# OpenHAS_SensorBoard_v1_0.net
KiCad netlist of a schematic drawn in EAGLE
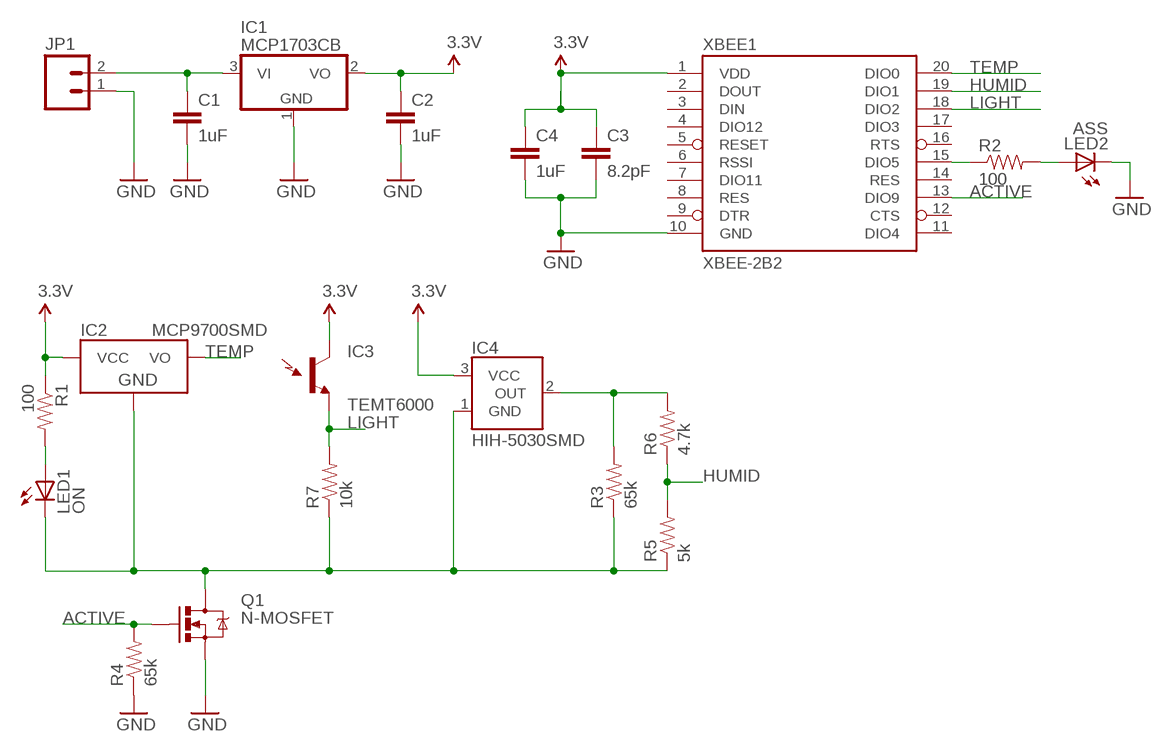
[diagram p0: schematic, sheet 1]

(export (version "E")
  (design (tool "Eeschema 10.0.6"))
  (components
    (comp (ref "C1")
      (value "1uF")
      (footprint "eagle-import:0805")
      (libsource (lib "eagle-import") (part "CAP0805"))
    )
    (comp (ref "C2")
      (value "1uF")
      (footprint "eagle-import:0805")
      (libsource (lib "eagle-import") (part "CAP0805"))
    )
    (comp (ref "C3")
      (value "8.2pF")
      (footprint "eagle-import:0805")
      (libsource (lib "eagle-import") (part "CAP0805"))
    )
    (comp (ref "C4")
      (value "1uF")
      (footprint "eagle-import:0805")
      (libsource (lib "eagle-import") (part "CAP0805"))
    )
    (comp (ref "IC1")
      (value "MCP1703CB")
      (footprint "eagle-import:SOT23")
      (libsource (lib "eagle-import") (part "MCP1703CB"))
    )
    (comp (ref "IC2")
      (value "MCP9700SMD")
      (footprint "eagle-import:SOT23-3")
      (libsource (lib "eagle-import") (part "MCP9700SMD"))
    )
    (comp (ref "IC3")
      (value "TEMT6000")
      (footprint "eagle-import:TEMT6000-SEN")
      (libsource (lib "eagle-import") (part "LIGHTSENSORTEMT6000"))
    )
    (comp (ref "IC4")
      (value "HIH-5030SMD")
      (footprint "eagle-import:HIH-4030")
      (libsource (lib "eagle-import") (part "HIH-4030SMD"))
    )
    (comp (ref "JP1")
      (value "M02POLAR")
      (footprint "eagle-import:MOLEX-1X2")
      (libsource (lib "eagle-import") (part "M02POLAR"))
    )
    (comp (ref "LED1")
      (value "ON")
      (footprint "eagle-import:CHIP-LED0805")
      (libsource (lib "eagle-import") (part "LEDCHIP-LED0805"))
    )
    (comp (ref "LED2")
      (value "ASS")
      (footprint "eagle-import:CHIP-LED0805")
      (libsource (lib "eagle-import") (part "LEDCHIP-LED0805"))
    )
    (comp (ref "Q1")
      (value "N-MOSFET")
      (footprint "eagle-import:SOT23-3")
      (libsource (lib "eagle-import") (part "MOSFET-NCHANNELAO3404A"))
    )
    (comp (ref "R1")
      (value "100")
      (footprint "eagle-import:0805")
      (libsource (lib "eagle-import") (part "RESISTOR0805-RES"))
    )
    (comp (ref "R2")
      (value "100")
      (footprint "eagle-import:0805")
      (libsource (lib "eagle-import") (part "SparkFun-Resistors_RESISTOR0805-RES"))
    )
    (comp (ref "R3")
      (value "65k")
      (footprint "eagle-import:0805")
      (libsource (lib "eagle-import") (part "SparkFun-Resistors_RESISTOR0805-RES"))
    )
    (comp (ref "R4")
      (value "65k")
      (footprint "eagle-import:0805")
      (libsource (lib "eagle-import") (part "SparkFun-Resistors_RESISTOR0805-RES"))
    )
    (comp (ref "R5")
      (value "5k")
      (footprint "eagle-import:0805")
      (libsource (lib "eagle-import") (part "SparkFun-Resistors_RESISTOR0805-RES"))
    )
    (comp (ref "R6")
      (value "4.7k")
      (footprint "eagle-import:0805")
      (libsource (lib "eagle-import") (part "SparkFun-Resistors_RESISTOR0805-RES"))
    )
    (comp (ref "R7")
      (value "10k")
      (footprint "eagle-import:0805")
      (libsource (lib "eagle-import") (part "SparkFun-Resistors_RESISTOR0805-RES"))
    )
    (comp (ref "XBEE1")
      (value "XBEE-2B2")
      (footprint "eagle-import:XBEE-SILK")
      (libsource (lib "eagle-import") (part "XBEE-2B2"))
    )
  )
  (nets
    (net (code "1") (name "/ACTIVE") (class "Default")
      (node (ref "Q1") (pin "1") (pinfunction "G_1") (pintype "passive"))
      (node (ref "R4") (pin "2") (pinfunction "2_2") (pintype "passive"))
      (node (ref "XBEE1") (pin "13") (pinfunction "DIO9_13") (pintype "bidirectional"))
    )
    (net (code "2") (name "/HUMID") (class "Default")
      (node (ref "R5") (pin "2") (pinfunction "2_2") (pintype "passive"))
      (node (ref "R6") (pin "1") (pinfunction "1_1") (pintype "passive"))
      (node (ref "XBEE1") (pin "19") (pinfunction "DIO1_19") (pintype "bidirectional"))
    )
    (net (code "3") (name "/LIGHT") (class "Default")
      (node (ref "IC3") (pin "EMITTER") (pinfunction "E1_EMITTER") (pintype "passive"))
      (node (ref "R7") (pin "2") (pinfunction "2_2") (pintype "passive"))
      (node (ref "XBEE1") (pin "18") (pinfunction "DIO2_18") (pintype "bidirectional"))
    )
    (net (code "4") (name "/TEMP") (class "Default")
      (node (ref "IC2") (pin "2") (pinfunction "VO_2") (pintype "bidirectional"))
      (node (ref "XBEE1") (pin "20") (pinfunction "DIO0_20") (pintype "bidirectional"))
    )
    (net (code "5") (name "3.3V") (class "Default")
      (node (ref "C2") (pin "1") (pinfunction "1_1") (pintype "passive"))
      (node (ref "C3") (pin "1") (pinfunction "1_1") (pintype "passive"))
      (node (ref "C4") (pin "1") (pinfunction "1_1") (pintype "passive"))
      (node (ref "IC1") (pin "2") (pinfunction "VO_2") (pintype "passive"))
      (node (ref "IC2") (pin "1") (pinfunction "VCC_1") (pintype "bidirectional"))
      (node (ref "IC3") (pin "COLLECTOR") (pinfunction "C1_COLLECTOR") (pintype "passive"))
      (node (ref "IC4") (pin "3") (pinfunction "VCC_3") (pintype "bidirectional"))
      (node (ref "R1") (pin "1") (pinfunction "1_1") (pintype "passive"))
      (node (ref "XBEE1") (pin "1") (pinfunction "VDD_1") (pintype "power_in"))
    )
    (net (code "6") (name "GND") (class "Default")
      (node (ref "C1") (pin "2") (pinfunction "2_2") (pintype "passive"))
      (node (ref "C2") (pin "2") (pinfunction "2_2") (pintype "passive"))
      (node (ref "C3") (pin "2") (pinfunction "2_2") (pintype "passive"))
      (node (ref "C4") (pin "2") (pinfunction "2_2") (pintype "passive"))
      (node (ref "IC1") (pin "1") (pinfunction "GND_1") (pintype "passive"))
      (node (ref "JP1") (pin "1") (pinfunction "1_1") (pintype "passive"))
      (node (ref "LED2") (pin "C") (pinfunction "C_C") (pintype "passive"))
      (node (ref "Q1") (pin "2") (pinfunction "S_2") (pintype "passive"))
      (node (ref "R4") (pin "1") (pinfunction "1_1") (pintype "passive"))
      (node (ref "XBEE1") (pin "10") (pinfunction "GND_10") (pintype "power_in"))
    )
    (net (code "7") (name "Net-(IC1-VI)") (class "Default")
      (node (ref "C1") (pin "1") (pinfunction "1_1") (pintype "passive"))
      (node (ref "IC1") (pin "3") (pinfunction "VI_3") (pintype "input"))
      (node (ref "JP1") (pin "2") (pinfunction "2_2") (pintype "passive"))
    )
    (net (code "8") (name "Net-(IC2-GND)") (class "Default")
      (node (ref "IC2") (pin "3") (pinfunction "GND_3") (pintype "bidirectional"))
      (node (ref "IC4") (pin "1") (pinfunction "GND_1") (pintype "bidirectional"))
      (node (ref "LED1") (pin "C") (pinfunction "C_C") (pintype "passive"))
      (node (ref "Q1") (pin "3") (pinfunction "D_3") (pintype "passive"))
      (node (ref "R3") (pin "1") (pinfunction "1_1") (pintype "passive"))
      (node (ref "R5") (pin "1") (pinfunction "1_1") (pintype "passive"))
      (node (ref "R7") (pin "1") (pinfunction "1_1") (pintype "passive"))
    )
    (net (code "9") (name "Net-(IC4-OUT)") (class "Default")
      (node (ref "IC4") (pin "2") (pinfunction "OUT_2") (pintype "bidirectional"))
      (node (ref "R3") (pin "2") (pinfunction "2_2") (pintype "passive"))
      (node (ref "R6") (pin "2") (pinfunction "2_2") (pintype "passive"))
    )
    (net (code "10") (name "Net-(LED1-PadA)") (class "Default")
      (node (ref "LED1") (pin "A") (pinfunction "A_A") (pintype "passive"))
      (node (ref "R1") (pin "2") (pinfunction "2_2") (pintype "passive"))
    )
    (net (code "11") (name "Net-(LED2-PadA)") (class "Default")
      (node (ref "LED2") (pin "A") (pinfunction "A_A") (pintype "passive"))
      (node (ref "R2") (pin "2") (pinfunction "2_2") (pintype "passive"))
    )
    (net (code "12") (name "Net-(XBEE1-DIO5)") (class "Default")
      (node (ref "R2") (pin "1") (pinfunction "1_1") (pintype "passive"))
      (node (ref "XBEE1") (pin "15") (pinfunction "DIO5_15") (pintype "bidirectional"))
    )
    (net (code "13") (name "unconnected-(XBEE1-CTS-Pad12)") (class "Default")
      (node (ref "XBEE1") (pin "12") (pinfunction "CTS_12") (pintype "output"))
    )
    (net (code "14") (name "unconnected-(XBEE1-DIN-Pad3)") (class "Default")
      (node (ref "XBEE1") (pin "3") (pinfunction "DIN_3") (pintype "input"))
    )
    (net (code "15") (name "unconnected-(XBEE1-DIO3-Pad17)") (class "Default")
      (node (ref "XBEE1") (pin "17") (pinfunction "DIO3_17") (pintype "bidirectional"))
    )
    (net (code "16") (name "unconnected-(XBEE1-DIO4-Pad11)") (class "Default")
      (node (ref "XBEE1") (pin "11") (pinfunction "DIO4_11") (pintype "bidirectional"))
    )
    (net (code "17") (name "unconnected-(XBEE1-DIO11-Pad7)") (class "Default")
      (node (ref "XBEE1") (pin "7") (pinfunction "DIO11_7") (pintype "bidirectional"))
    )
    (net (code "18") (name "unconnected-(XBEE1-DIO12-Pad4)") (class "Default")
      (node (ref "XBEE1") (pin "4") (pinfunction "DIO12_4") (pintype "bidirectional"))
    )
    (net (code "19") (name "unconnected-(XBEE1-DOUT-Pad2)") (class "Default")
      (node (ref "XBEE1") (pin "2") (pinfunction "DOUT_2") (pintype "output"))
    )
    (net (code "20") (name "unconnected-(XBEE1-DTR-Pad9)") (class "Default")
      (node (ref "XBEE1") (pin "9") (pinfunction "DTR_9") (pintype "bidirectional"))
    )
    (net (code "21") (name "unconnected-(XBEE1-RES-Pad8)") (class "Default")
      (node (ref "XBEE1") (pin "8") (pinfunction "RES_8") (pintype "bidirectional"))
    )
    (net (code "22") (name "unconnected-(XBEE1-RES-Pad14)") (class "Default")
      (node (ref "XBEE1") (pin "14") (pinfunction "RES_14") (pintype "bidirectional"))
    )
    (net (code "23") (name "unconnected-(XBEE1-RESET-Pad5)") (class "Default")
      (node (ref "XBEE1") (pin "5") (pinfunction "RESET_5") (pintype "input"))
    )
    (net (code "24") (name "unconnected-(XBEE1-RSSI-Pad6)") (class "Default")
      (node (ref "XBEE1") (pin "6") (pinfunction "RSSI_6") (pintype "bidirectional"))
    )
    (net (code "25") (name "unconnected-(XBEE1-RTS-Pad16)") (class "Default")
      (node (ref "XBEE1") (pin "16") (pinfunction "RTS_16") (pintype "input"))
    )
  )
)
